# id_eeprom.net
KiCad netlist of a schematic drawn in Altium Designer
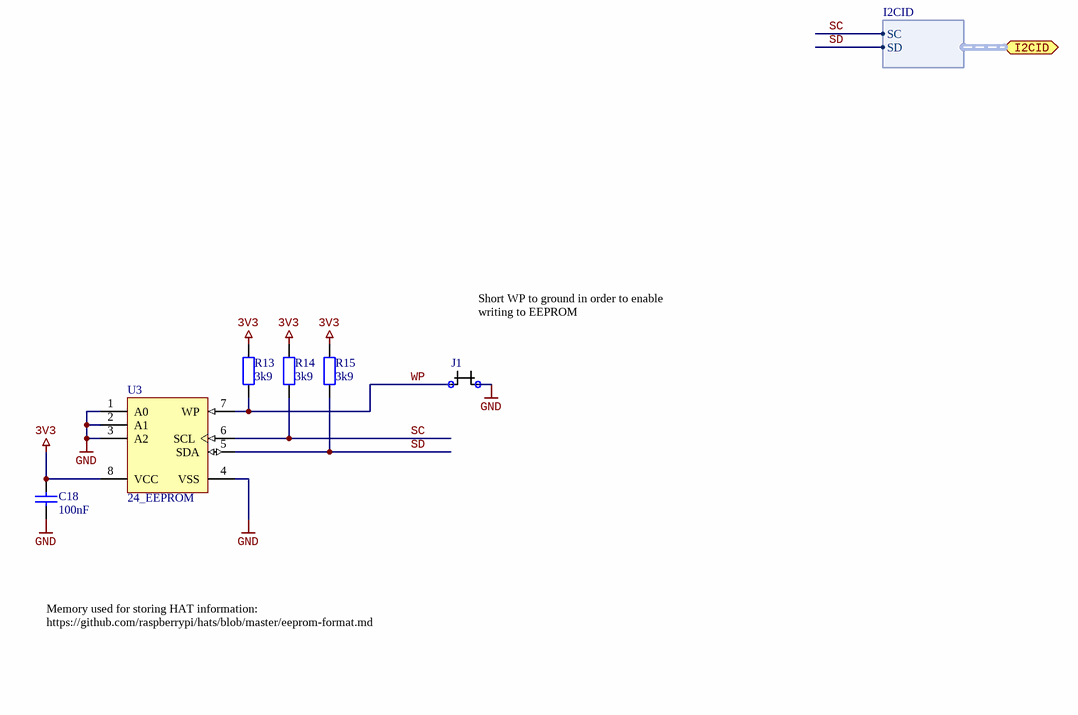
[diagram p0: id_eeprom.SchDoc]

(export (version "E")
  (design (tool "Eeschema 10.0.6"))
  (components
    (comp (ref "C18")
      (value "100nF")
      (footprint "CAPC1608N")
      (description "Capacitor")
      (libsource (lib "Discrete") (part "Capacitor"))
    )
    (comp (ref "J1")
      (value "Jumper")
      (footprint "JUMPER")
      (libsource (lib "my_various_devices") (part "Jumper"))
    )
    (comp (ref "R13")
      (value "3k9")
      (footprint "Chip_Resistor_N:RESC1608N")
      (description "Resistor")
      (fields (field (name "TOLERANCE") "5%") (field (name "POWER") "0W"))
      (libsource (lib "Discrete") (part "Resistor"))
    )
    (comp (ref "R14")
      (value "3k9")
      (footprint "Chip_Resistor_N:RESC1608N")
      (description "Resistor")
      (fields (field (name "TOLERANCE") "5%") (field (name "POWER") "0W"))
      (libsource (lib "Discrete") (part "Resistor"))
    )
    (comp (ref "R15")
      (value "3k9")
      (footprint "Chip_Resistor_N:RESC1608N")
      (description "Resistor")
      (fields (field (name "TOLERANCE") "5%") (field (name "POWER") "0W"))
      (libsource (lib "Discrete") (part "Resistor"))
    )
    (comp (ref "U3")
      (value "24_EEPROM")
      (footprint "SO-8_L")
      (description "16Kbit, 400kHz, 2.5V, I2C Serial EEPROM, 8-Pin SOIC 150mil, Extended Temperature")
      (libsource (lib "my_various_devices") (part "24_EEPROM"))
    )
  )
  (nets
    (net (code "2") (name "/SC") (class "Default")
      (node (ref "R14") (pin "2") (pinfunction "2_2") (pintype "passive"))
      (node (ref "U3") (pin "6") (pinfunction "SCL_6") (pintype "input"))
    )
    (net (code "3") (name "/SD") (class "Default")
      (node (ref "R15") (pin "2") (pinfunction "2_2") (pintype "passive"))
      (node (ref "U3") (pin "5") (pinfunction "SDA_5") (pintype "bidirectional"))
    )
    (net (code "4") (name "/WP") (class "Default")
      (node (ref "J1") (pin "1") (pinfunction "1_1") (pintype "passive"))
      (node (ref "R13") (pin "2") (pinfunction "2_2") (pintype "passive"))
      (node (ref "U3") (pin "7") (pinfunction "WP_7") (pintype "input"))
    )
    (net (code "6") (name "3V3") (class "Default")
      (node (ref "C18") (pin "2") (pinfunction "2_2") (pintype "passive"))
      (node (ref "R13") (pin "1") (pinfunction "1_1") (pintype "passive"))
      (node (ref "R14") (pin "1") (pinfunction "1_1") (pintype "passive"))
      (node (ref "R15") (pin "1") (pinfunction "1_1") (pintype "passive"))
      (node (ref "U3") (pin "8") (pinfunction "VCC_8") (pintype "power_in"))
    )
    (net (code "7") (name "GND") (class "Default")
      (node (ref "C18") (pin "1") (pinfunction "1_1") (pintype "passive"))
      (node (ref "J1") (pin "2") (pinfunction "2_2") (pintype "passive"))
      (node (ref "U3") (pin "1") (pinfunction "A0_1") (pintype "passive"))
      (node (ref "U3") (pin "2") (pinfunction "A1_2") (pintype "passive"))
      (node (ref "U3") (pin "3") (pinfunction "A2_3") (pintype "passive"))
      (node (ref "U3") (pin "4") (pinfunction "VSS_4") (pintype "power_in"))
    )
  )
)
